# Loginator2368.net
KiCad netlist of a schematic drawn in EAGLE
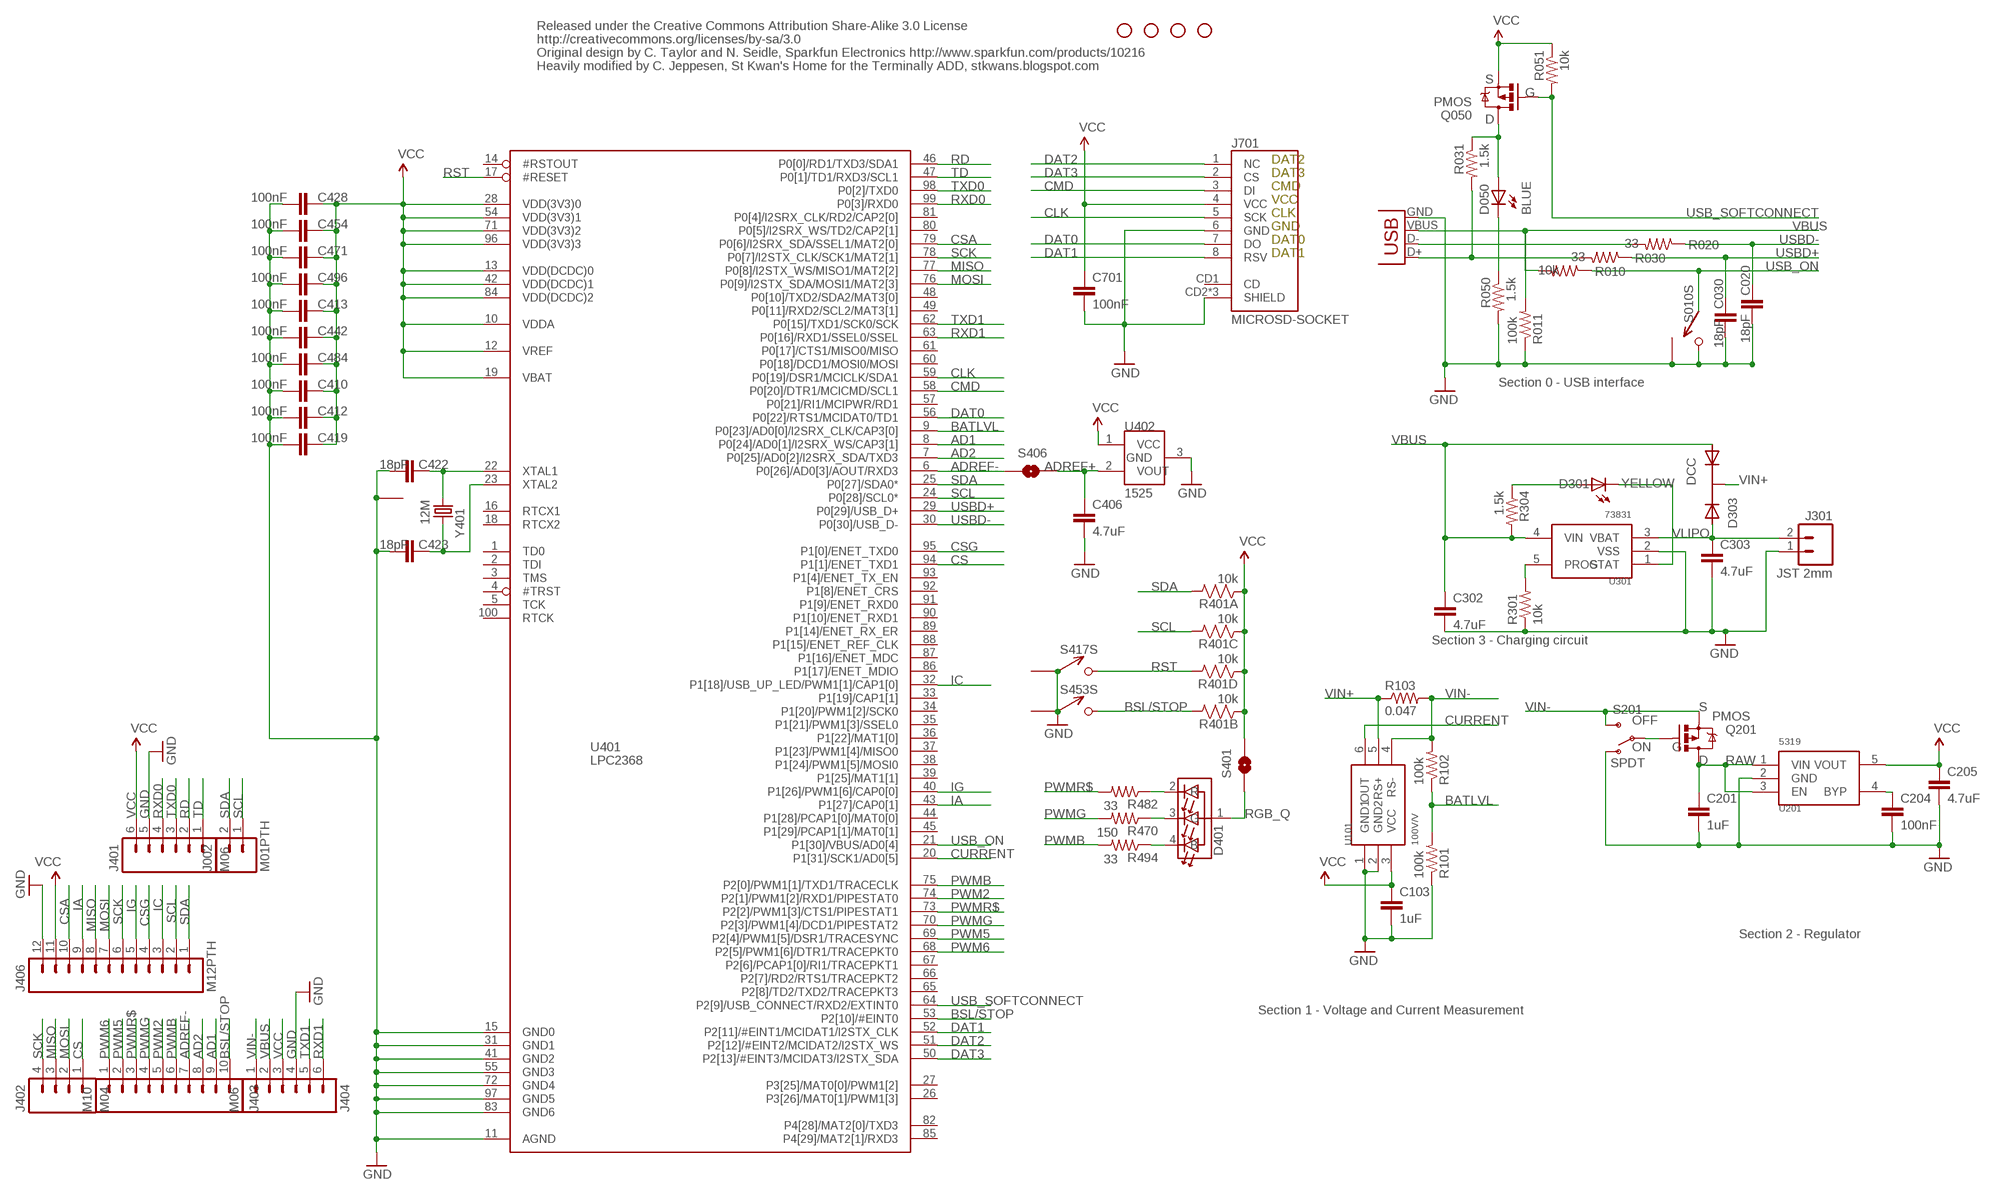
[diagram p0: schematic, sheet 1]

(export (version "E")
  (design (tool "Eeschema 10.0.6"))
  (components
    (comp (ref "C020")
      (value "18pF")
      (footprint "eagle-import:0402-CAP")
      (libsource (lib "eagle-import") (part "CAP0402-CAP"))
    )
    (comp (ref "C030")
      (value "18pF")
      (footprint "eagle-import:0402-CAP")
      (libsource (lib "eagle-import") (part "CAP0402-CAP"))
    )
    (comp (ref "C103")
      (value "1uF")
      (footprint "eagle-import:0402-CAP")
      (libsource (lib "eagle-import") (part "CAP0402-CAP"))
    )
    (comp (ref "C201")
      (value "1uF")
      (footprint "eagle-import:0402-CAP")
      (libsource (lib "eagle-import") (part "CAP0402-CAP"))
    )
    (comp (ref "C204")
      (value "100nF")
      (footprint "eagle-import:0402-CAP")
      (libsource (lib "eagle-import") (part "CAP0402-CAP"))
    )
    (comp (ref "C205")
      (value "4.7uF")
      (footprint "eagle-import:0402-CAP")
      (libsource (lib "eagle-import") (part "CAP0402-CAP"))
    )
    (comp (ref "C302")
      (value "4.7uF")
      (footprint "eagle-import:0402-CAP")
      (libsource (lib "eagle-import") (part "CAP0402-CAP"))
    )
    (comp (ref "C303")
      (value "4.7uF")
      (footprint "eagle-import:0402-CAP")
      (libsource (lib "eagle-import") (part "CAP0402-CAP"))
    )
    (comp (ref "C406")
      (value "4.7uF")
      (footprint "eagle-import:0402-CAP")
      (libsource (lib "eagle-import") (part "CAP0402-CAP"))
    )
    (comp (ref "C410")
      (value "100nF")
      (footprint "eagle-import:0402-CAP")
      (libsource (lib "eagle-import") (part "CAP0402-CAP"))
    )
    (comp (ref "C412")
      (value "100nF")
      (footprint "eagle-import:0402-CAP")
      (libsource (lib "eagle-import") (part "CAP0402-CAP"))
    )
    (comp (ref "C413")
      (value "100nF")
      (footprint "eagle-import:0402-CAP")
      (libsource (lib "eagle-import") (part "CAP0402-CAP"))
    )
    (comp (ref "C419")
      (value "100nF")
      (footprint "eagle-import:0402-CAP")
      (libsource (lib "eagle-import") (part "CAP0402-CAP"))
    )
    (comp (ref "C422")
      (value "18pF")
      (footprint "eagle-import:0402-CAP")
      (libsource (lib "eagle-import") (part "CAP0402-CAP"))
    )
    (comp (ref "C423")
      (value "18pF")
      (footprint "eagle-import:0402-CAP")
      (libsource (lib "eagle-import") (part "CAP0402-CAP"))
    )
    (comp (ref "C428")
      (value "100nF")
      (footprint "eagle-import:0402-CAP")
      (libsource (lib "eagle-import") (part "CAP0402-CAP"))
    )
    (comp (ref "C442")
      (value "100nF")
      (footprint "eagle-import:0402-CAP")
      (libsource (lib "eagle-import") (part "CAP0402-CAP"))
    )
    (comp (ref "C454")
      (value "100nF")
      (footprint "eagle-import:0402-CAP")
      (libsource (lib "eagle-import") (part "CAP0402-CAP"))
    )
    (comp (ref "C471")
      (value "100nF")
      (footprint "eagle-import:0402-CAP")
      (libsource (lib "eagle-import") (part "CAP0402-CAP"))
    )
    (comp (ref "C484")
      (value "100nF")
      (footprint "eagle-import:0402-CAP")
      (libsource (lib "eagle-import") (part "CAP0402-CAP"))
    )
    (comp (ref "C496")
      (value "100nF")
      (footprint "eagle-import:0402-CAP")
      (libsource (lib "eagle-import") (part "CAP0402-CAP"))
    )
    (comp (ref "C701")
      (value "100nF")
      (footprint "eagle-import:0402-CAP")
      (libsource (lib "eagle-import") (part "CAP0402-CAP"))
    )
    (comp (ref "D050")
      (value "BLUE")
      (footprint "eagle-import:LED-0603")
      (libsource (lib "eagle-import") (part "LED0603"))
    )
    (comp (ref "D301")
      (value "YELLOW")
      (footprint "eagle-import:LED-0603")
      (libsource (lib "eagle-import") (part "LED0603"))
    )
    (comp (ref "D303")
      (value "DCC")
      (footprint "eagle-import:SOT-23-3")
      (libsource (lib "eagle-import") (part "PMEG2005CT"))
    )
    (comp (ref "D401")
      (value "RGB")
      (footprint "eagle-import:HSMF-C118")
      (libsource (lib "eagle-import") (part "HSMF-C118"))
    )
    (comp (ref "J001")
      (value "USBSMD")
      (footprint "eagle-import:USB-MINIB")
      (libsource (lib "eagle-import") (part "USBSMD"))
    )
    (comp (ref "J002")
      (value "M01PTH")
      (footprint "eagle-import:1X02")
      (libsource (lib "eagle-import") (part "M02PTH"))
    )
    (comp (ref "J301")
      (value "JST 2mm")
      (footprint "eagle-import:JST-2-SMD")
      (libsource (lib "eagle-import") (part "M02-JST-2MM-SMT"))
    )
    (comp (ref "J401")
      (value "M06")
      (footprint "eagle-import:1X06")
      (libsource (lib "eagle-import") (part "M06SIP"))
    )
    (comp (ref "J402")
      (value "M04")
      (footprint "eagle-import:1X04")
      (libsource (lib "eagle-import") (part "M04PTH"))
    )
    (comp (ref "J403")
      (value "M10")
      (footprint "eagle-import:1X10")
      (libsource (lib "eagle-import") (part "M10{dblquote}"))
    )
    (comp (ref "J404")
      (value "M06")
      (footprint "eagle-import:1X06")
      (libsource (lib "eagle-import") (part "M06SIP"))
    )
    (comp (ref "J406")
      (value "M12PTH")
      (footprint "eagle-import:1X12")
      (libsource (lib "eagle-import") (part "M12PTH"))
    )
    (comp (ref "J701")
      (value "MICROSD-SOCKET")
      (footprint "eagle-import:MICROSD-SOCKET-PP")
      (libsource (lib "eagle-import") (part "MICROSD-SOCKET"))
    )
    (comp (ref "JP1")
      (value "STAND-OFF")
      (footprint "eagle-import:STAND-OFF")
      (libsource (lib "eagle-import") (part "STAND-OFF"))
    )
    (comp (ref "JP2")
      (value "STAND-OFF")
      (footprint "eagle-import:STAND-OFF")
      (libsource (lib "eagle-import") (part "STAND-OFF"))
    )
    (comp (ref "JP3")
      (value "STAND-OFF")
      (footprint "eagle-import:STAND-OFF")
      (libsource (lib "eagle-import") (part "STAND-OFF"))
    )
    (comp (ref "JP4")
      (value "STAND-OFF")
      (footprint "eagle-import:STAND-OFF")
      (libsource (lib "eagle-import") (part "STAND-OFF"))
    )
    (comp (ref "Q050")
      (value "PMOS")
      (footprint "eagle-import:SOT23-3")
      (libsource (lib "eagle-import") (part "MOSFET-PCHANNELSMD"))
    )
    (comp (ref "Q201")
      (value "PMOS")
      (footprint "eagle-import:SOT23-3")
      (libsource (lib "eagle-import") (part "MOSFET-PCHANNELSMD"))
    )
    (comp (ref "R010")
      (value "10k")
      (footprint "eagle-import:0402-RES")
      (libsource (lib "eagle-import") (part "RESISTOR0402-RES"))
    )
    (comp (ref "R011")
      (value "100k")
      (footprint "eagle-import:0402-RES")
      (libsource (lib "eagle-import") (part "RESISTOR0402-RES"))
    )
    (comp (ref "R020")
      (value "33")
      (footprint "eagle-import:0402-RES")
      (libsource (lib "eagle-import") (part "RESISTOR0402-RES"))
    )
    (comp (ref "R030")
      (value "33")
      (footprint "eagle-import:0402-RES")
      (libsource (lib "eagle-import") (part "RESISTOR0402-RES"))
    )
    (comp (ref "R031")
      (value "1.5k")
      (footprint "eagle-import:0402-RES")
      (libsource (lib "eagle-import") (part "RESISTOR0402-RES"))
    )
    (comp (ref "R050")
      (value "1.5k")
      (footprint "eagle-import:0402-RES")
      (libsource (lib "eagle-import") (part "RESISTOR0402-RES"))
    )
    (comp (ref "R051")
      (value "10k")
      (footprint "eagle-import:0402-RES")
      (libsource (lib "eagle-import") (part "RESISTOR0402-RES"))
    )
    (comp (ref "R101")
      (value "100k")
      (footprint "eagle-import:0402-RES")
      (libsource (lib "eagle-import") (part "RESISTOR0402-RES"))
    )
    (comp (ref "R102")
      (value "100k")
      (footprint "eagle-import:0402-RES")
      (libsource (lib "eagle-import") (part "RESISTOR0402-RES"))
    )
    (comp (ref "R103")
      (value "0.047")
      (footprint "eagle-import:0402-RES")
      (libsource (lib "eagle-import") (part "RESISTOR0402-RES"))
    )
    (comp (ref "R301")
      (value "10k")
      (footprint "eagle-import:0402-RES")
      (libsource (lib "eagle-import") (part "RESISTOR0402-RES"))
    )
    (comp (ref "R304")
      (value "1.5k")
      (footprint "eagle-import:0402-RES")
      (libsource (lib "eagle-import") (part "RESISTOR0402-RES"))
    )
    (comp (ref "R401")
      (value "10k")
      (footprint "eagle-import:CRA04")
      (fields (field (name "DIGIKEY") "CRA4S810KCT-ND"))
      (libsource (lib "eagle-import") (part "RP404"))
    )
    (comp (ref "R470")
      (value "150")
      (footprint "eagle-import:0402-RES")
      (libsource (lib "eagle-import") (part "RESISTOR0402-RES"))
    )
    (comp (ref "R482")
      (value "33")
      (footprint "eagle-import:0402-RES")
      (libsource (lib "eagle-import") (part "RESISTOR0402-RES"))
    )
    (comp (ref "R494")
      (value "33")
      (footprint "eagle-import:0402-RES")
      (libsource (lib "eagle-import") (part "RESISTOR0402-RES"))
    )
    (comp (ref "S010")
      (value "SPST")
      (footprint "eagle-import:B3U-1100P")
      (fields (field (name "DIGIKEY") "SW1021CT-ND"))
      (libsource (lib "eagle-import") (part "B3U-1100P"))
    )
    (comp (ref "S201")
      (value "SPDT")
      (footprint "eagle-import:AYZ0202")
      (libsource (lib "eagle-import") (part "SWITCH-SPSTSMD"))
    )
    (comp (ref "S401")
      (value "SOLDERJUMPERNO")
      (footprint "eagle-import:SJ_2S-NO")
      (libsource (lib "eagle-import") (part "SOLDERJUMPERNO"))
    )
    (comp (ref "S406")
      (value "SOLDERJUMPERNO")
      (footprint "eagle-import:SJ_2S-NO")
      (libsource (lib "eagle-import") (part "SOLDERJUMPERNO"))
    )
    (comp (ref "S417")
      (value "SPST")
      (footprint "eagle-import:B3U-1100P")
      (fields (field (name "DIGIKEY") "SW1021CT-ND"))
      (libsource (lib "eagle-import") (part "B3U-1100P"))
    )
    (comp (ref "S453")
      (value "SPST")
      (footprint "eagle-import:B3U-1100P")
      (fields (field (name "DIGIKEY") "SW1021CT-ND"))
      (libsource (lib "eagle-import") (part "B3U-1100P"))
    )
    (comp (ref "U101")
      (value "100V/V")
      (footprint "eagle-import:SOT-23-6")
      (libsource (lib "eagle-import") (part "MAX4173"))
    )
    (comp (ref "U201")
      (value "5319")
      (footprint "eagle-import:SOT-23-5")
      (libsource (lib "eagle-import") (part "MIC5319D5"))
    )
    (comp (ref "U301")
      (value "73831")
      (footprint "eagle-import:SOT-23-5")
      (libsource (lib "eagle-import") (part "MCP73831"))
    )
    (comp (ref "U401")
      (value "LPC2368")
      (footprint "eagle-import:LQFP100")
      (libsource (lib "eagle-import") (part "LPC2368"))
    )
    (comp (ref "U402")
      (value "1525")
      (footprint "eagle-import:SOT-23-3")
      (libsource (lib "eagle-import") (part "MCP1525"))
    )
    (comp (ref "Y401")
      (value "12M")
      (footprint "eagle-import:CRYSTAL_SMD")
      (fields (field (name "DIGIKEY") "887-1316-1-ND"))
      (libsource (lib "eagle-import") (part "TSX-3225"))
    )
  )
  (nets
    (net (code "1") (name "/AD1") (class "Default")
      (node (ref "J403") (pin "9") (pinfunction "9_9") (pintype "passive"))
      (node (ref "U401") (pin "8") (pinfunction "P0[24]/AD0[1]/I2SRX_WS/CAP3[1]_8") (pintype "bidirectional"))
    )
    (net (code "2") (name "/AD2") (class "Default")
      (node (ref "J403") (pin "8") (pinfunction "8_8") (pintype "passive"))
      (node (ref "U401") (pin "7") (pinfunction "P0[25]/AD0[2]/I2SRX_SDA/TXD3_7") (pintype "bidirectional"))
    )
    (net (code "3") (name "/ADREF+") (class "Default")
      (node (ref "C406") (pin "1") (pinfunction "1_1") (pintype "passive"))
      (node (ref "S406") (pin "1") (pinfunction "1_1") (pintype "passive"))
      (node (ref "U402") (pin "2") (pinfunction "VOUT_2") (pintype "bidirectional"))
    )
    (net (code "4") (name "/ADREF-") (class "Default")
      (node (ref "J403") (pin "7") (pinfunction "7_7") (pintype "passive"))
      (node (ref "S406") (pin "2") (pinfunction "2_2") (pintype "passive"))
      (node (ref "U401") (pin "6") (pinfunction "P0[26]/AD0[3]/AOUT/RXD3_6") (pintype "bidirectional"))
    )
    (net (code "5") (name "/BATLVL") (class "Default")
      (node (ref "R101") (pin "2") (pinfunction "2_2") (pintype "passive"))
      (node (ref "R102") (pin "1") (pinfunction "1_1") (pintype "passive"))
      (node (ref "U401") (pin "9") (pinfunction "P0[23]/AD0[0]/I2SRX_CLK/CAP3[0]_9") (pintype "bidirectional"))
    )
    (net (code "6") (name "/BSL{slash}STOP") (class "Default")
      (node (ref "J403") (pin "10") (pinfunction "10_10") (pintype "passive"))
      (node (ref "R401") (pin "7") (pinfunction "2_7") (pintype "passive"))
      (node (ref "S453") (pin "P$2") (pinfunction "2_P$2") (pintype "bidirectional"))
      (node (ref "U401") (pin "53") (pinfunction "P2[10]/#EINT0_53") (pintype "bidirectional"))
    )
    (net (code "7") (name "/CLK") (class "Default")
      (node (ref "J701") (pin "5") (pinfunction "SCK_5") (pintype "bidirectional"))
      (node (ref "U401") (pin "59") (pinfunction "P0[19]/DSR1/MCICLK/SDA1_59") (pintype "bidirectional"))
    )
    (net (code "8") (name "/CMD") (class "Default")
      (node (ref "J701") (pin "3") (pinfunction "DI_3") (pintype "bidirectional"))
      (node (ref "U401") (pin "58") (pinfunction "P0[20]/DTR1/MCICMD/SCL1_58") (pintype "bidirectional"))
    )
    (net (code "9") (name "/CS") (class "Default")
      (node (ref "J402") (pin "1") (pinfunction "1_1") (pintype "passive"))
      (node (ref "U401") (pin "94") (pinfunction "P1[1]/ENET_TXD1_94") (pintype "bidirectional"))
    )
    (net (code "10") (name "/CSA") (class "Default")
      (node (ref "J406") (pin "10") (pinfunction "10_10") (pintype "passive"))
      (node (ref "U401") (pin "79") (pinfunction "P0[6]/I2SRX_SDA/SSEL1/MAT2[0]_79") (pintype "bidirectional"))
    )
    (net (code "11") (name "/CSG") (class "Default")
      (node (ref "J406") (pin "4") (pinfunction "4_4") (pintype "passive"))
      (node (ref "U401") (pin "95") (pinfunction "P1[0]/ENET_TXD0_95") (pintype "bidirectional"))
    )
    (net (code "12") (name "/CURRENT") (class "Default")
      (node (ref "U101") (pin "6") (pinfunction "OUT_6") (pintype "bidirectional"))
      (node (ref "U401") (pin "20") (pinfunction "P1[31]/SCK1/AD0[5]_20") (pintype "bidirectional"))
    )
    (net (code "13") (name "/DAT0") (class "Default")
      (node (ref "J701") (pin "7") (pinfunction "DO_7") (pintype "bidirectional"))
      (node (ref "U401") (pin "56") (pinfunction "P0[22]/RTS1/MCIDAT0/TD1_56") (pintype "bidirectional"))
    )
    (net (code "14") (name "/DAT1") (class "Default")
      (node (ref "J701") (pin "8") (pinfunction "RSV_8") (pintype "bidirectional"))
      (node (ref "U401") (pin "52") (pinfunction "P2[11]/#EINT1/MCIDAT1/I2STX_CLK_52") (pintype "bidirectional"))
    )
    (net (code "15") (name "/DAT2") (class "Default")
      (node (ref "J701") (pin "1") (pinfunction "NC_1") (pintype "bidirectional"))
      (node (ref "U401") (pin "51") (pinfunction "P2[12]/#EINT2/MCIDAT2/I2STX_WS_51") (pintype "bidirectional"))
    )
    (net (code "16") (name "/DAT3") (class "Default")
      (node (ref "J701") (pin "2") (pinfunction "CS_2") (pintype "bidirectional"))
      (node (ref "U401") (pin "50") (pinfunction "P2[13]/#EINT3/MCIDAT3/I2STX_SDA_50") (pintype "bidirectional"))
    )
    (net (code "17") (name "/IA") (class "Default")
      (node (ref "J406") (pin "9") (pinfunction "9_9") (pintype "passive"))
      (node (ref "U401") (pin "43") (pinfunction "P1[27]/CAP0[1]_43") (pintype "bidirectional"))
    )
    (net (code "18") (name "/IC") (class "Default")
      (node (ref "J406") (pin "3") (pinfunction "3_3") (pintype "passive"))
      (node (ref "U401") (pin "32") (pinfunction "P1[18]/USB_UP_LED/PWM1[1]/CAP1[0]_32") (pintype "bidirectional"))
    )
    (net (code "19") (name "/IG") (class "Default")
      (node (ref "J406") (pin "5") (pinfunction "5_5") (pintype "passive"))
      (node (ref "U401") (pin "40") (pinfunction "P1[26]/PWM1[6]/CAP0[0]_40") (pintype "bidirectional"))
    )
    (net (code "20") (name "/MISO") (class "Default")
      (node (ref "J402") (pin "3") (pinfunction "3_3") (pintype "passive"))
      (node (ref "J406") (pin "8") (pinfunction "8_8") (pintype "passive"))
      (node (ref "U401") (pin "77") (pinfunction "P0[8]/I2STX_WS/MISO1/MAT2[2]_77") (pintype "bidirectional"))
    )
    (net (code "21") (name "/MOSI") (class "Default")
      (node (ref "J402") (pin "2") (pinfunction "2_2") (pintype "passive"))
      (node (ref "J406") (pin "7") (pinfunction "7_7") (pintype "passive"))
      (node (ref "U401") (pin "76") (pinfunction "P0[9]/I2STX_SDA/MOSI1/MAT2[3]_76") (pintype "bidirectional"))
    )
    (net (code "22") (name "/PWM2") (class "Default")
      (node (ref "J403") (pin "5") (pinfunction "5_5") (pintype "passive"))
      (node (ref "U401") (pin "74") (pinfunction "P2[1]/PWM1[2]/RXD1/PIPESTAT0_74") (pintype "bidirectional"))
    )
    (net (code "23") (name "/PWM5") (class "Default")
      (node (ref "J403") (pin "2") (pinfunction "2_2") (pintype "passive"))
      (node (ref "U401") (pin "69") (pinfunction "P2[4]/PWM1[5]/DSR1/TRACESYNC_69") (pintype "bidirectional"))
    )
    (net (code "24") (name "/PWM6") (class "Default")
      (node (ref "J403") (pin "1") (pinfunction "1_1") (pintype "passive"))
      (node (ref "U401") (pin "68") (pinfunction "P2[5]/PWM1[6]/DTR1/TRACEPKT0_68") (pintype "bidirectional"))
    )
    (net (code "25") (name "/PWMB") (class "Default")
      (node (ref "J403") (pin "6") (pinfunction "6_6") (pintype "passive"))
      (node (ref "R494") (pin "2") (pinfunction "2_2") (pintype "passive"))
      (node (ref "U401") (pin "75") (pinfunction "P2[0]/PWM1[1]/TXD1/TRACECLK_75") (pintype "bidirectional"))
    )
    (net (code "26") (name "/PWMG") (class "Default")
      (node (ref "J403") (pin "4") (pinfunction "4_4") (pintype "passive"))
      (node (ref "R470") (pin "2") (pinfunction "2_2") (pintype "passive"))
      (node (ref "U401") (pin "70") (pinfunction "P2[3]/PWM1[4]/DCD1/PIPESTAT2_70") (pintype "bidirectional"))
    )
    (net (code "27") (name "/PWMR$") (class "Default")
      (node (ref "J403") (pin "3") (pinfunction "3_3") (pintype "passive"))
      (node (ref "R482") (pin "2") (pinfunction "2_2") (pintype "passive"))
      (node (ref "U401") (pin "73") (pinfunction "P2[2]/PWM1[3]/CTS1/PIPESTAT1_73") (pintype "bidirectional"))
    )
    (net (code "28") (name "/RAW") (class "Default")
      (node (ref "C201") (pin "1") (pinfunction "1_1") (pintype "passive"))
      (node (ref "Q201") (pin "3") (pinfunction "D_3") (pintype "passive"))
      (node (ref "U201") (pin "1") (pinfunction "VIN_1") (pintype "bidirectional"))
      (node (ref "U201") (pin "3") (pinfunction "EN_3") (pintype "bidirectional"))
    )
    (net (code "29") (name "/RD") (class "Default")
      (node (ref "J401") (pin "2") (pinfunction "2_2") (pintype "passive"))
      (node (ref "U401") (pin "46") (pinfunction "P0[0]/RD1/TXD3/SDA1_46") (pintype "bidirectional"))
    )
    (net (code "30") (name "/RGB_Q") (class "Default")
      (node (ref "D401") (pin "1") (pinfunction "A_1") (pintype "passive"))
      (node (ref "S401") (pin "1") (pinfunction "1_1") (pintype "passive"))
    )
    (net (code "31") (name "/RST") (class "Default")
      (node (ref "R401") (pin "5") (pinfunction "2_5") (pintype "passive"))
      (node (ref "S417") (pin "P$2") (pinfunction "2_P$2") (pintype "bidirectional"))
      (node (ref "U401") (pin "17") (pinfunction "#RESET_17") (pintype "bidirectional"))
    )
    (net (code "32") (name "/RXD0") (class "Default")
      (node (ref "J401") (pin "4") (pinfunction "4_4") (pintype "passive"))
      (node (ref "U401") (pin "99") (pinfunction "P0[3]/RXD0_99") (pintype "bidirectional"))
    )
    (net (code "33") (name "/RXD1") (class "Default")
      (node (ref "J404") (pin "6") (pinfunction "6_6") (pintype "passive"))
      (node (ref "U401") (pin "63") (pinfunction "P0[16]/RXD1/SSEL0/SSEL_63") (pintype "bidirectional"))
    )
    (net (code "34") (name "/SCK") (class "Default")
      (node (ref "J402") (pin "4") (pinfunction "4_4") (pintype "passive"))
      (node (ref "J406") (pin "6") (pinfunction "6_6") (pintype "passive"))
      (node (ref "U401") (pin "78") (pinfunction "P0[7]/I2STX_CLK/SCK1/MAT2[1]_78") (pintype "bidirectional"))
    )
    (net (code "35") (name "/SCL") (class "Default")
      (node (ref "J002") (pin "1") (pinfunction "1_1") (pintype "passive"))
      (node (ref "J406") (pin "2") (pinfunction "2_2") (pintype "passive"))
      (node (ref "R401") (pin "6") (pinfunction "2_6") (pintype "passive"))
      (node (ref "U401") (pin "24") (pinfunction "P0[28]/SCL0*_24") (pintype "bidirectional"))
    )
    (net (code "36") (name "/SDA") (class "Default")
      (node (ref "J002") (pin "2") (pinfunction "2_2") (pintype "passive"))
      (node (ref "J406") (pin "1") (pinfunction "1_1") (pintype "passive"))
      (node (ref "R401") (pin "8") (pinfunction "2_8") (pintype "passive"))
      (node (ref "U401") (pin "25") (pinfunction "P0[27]/SDA0*_25") (pintype "bidirectional"))
    )
    (net (code "37") (name "/TD") (class "Default")
      (node (ref "J401") (pin "1") (pinfunction "1_1") (pintype "passive"))
      (node (ref "U401") (pin "47") (pinfunction "P0[1]/TD1/RXD3/SCL1_47") (pintype "bidirectional"))
    )
    (net (code "38") (name "/TXD0") (class "Default")
      (node (ref "J401") (pin "3") (pinfunction "3_3") (pintype "passive"))
      (node (ref "U401") (pin "98") (pinfunction "P0[2]/TXD0_98") (pintype "bidirectional"))
    )
    (net (code "39") (name "/TXD1") (class "Default")
      (node (ref "J404") (pin "5") (pinfunction "5_5") (pintype "passive"))
      (node (ref "U401") (pin "62") (pinfunction "P0[15]/TXD1/SCK0/SCK_62") (pintype "bidirectional"))
    )
    (net (code "40") (name "/USBD+") (class "Default")
      (node (ref "C030") (pin "1") (pinfunction "1_1") (pintype "passive"))
      (node (ref "R030") (pin "1") (pinfunction "1_1") (pintype "passive"))
      (node (ref "U401") (pin "29") (pinfunction "P0[29]/USB_D+_29") (pintype "bidirectional"))
    )
    (net (code "41") (name "/USBD-") (class "Default")
      (node (ref "C020") (pin "1") (pinfunction "1_1") (pintype "passive"))
      (node (ref "R020") (pin "1") (pinfunction "1_1") (pintype "passive"))
      (node (ref "U401") (pin "30") (pinfunction "P0[30]/USB_D-_30") (pintype "bidirectional"))
    )
    (net (code "42") (name "/USB_ON") (class "Default")
      (node (ref "R010") (pin "1") (pinfunction "1_1") (pintype "passive"))
      (node (ref "S010") (pin "P$1") (pinfunction "1_P$1") (pintype "bidirectional"))
      (node (ref "U401") (pin "21") (pinfunction "P1[30]/VBUS/AD0[4]_21") (pintype "bidirectional"))
    )
    (net (code "43") (name "/USB_SOFTCONNECT") (class "Default")
      (node (ref "Q050") (pin "1") (pinfunction "G_1") (pintype "passive"))
      (node (ref "R051") (pin "2") (pinfunction "2_2") (pintype "passive"))
      (node (ref "U401") (pin "64") (pinfunction "P2[9]/USB_CONNECT/RXD2/EXTINT0_64") (pintype "bidirectional"))
    )
    (net (code "44") (name "/VBUS") (class "Default")
      (node (ref "C302") (pin "1") (pinfunction "1_1") (pintype "passive"))
      (node (ref "D303") (pin "1") (pinfunction "A1_1") (pintype "passive"))
      (node (ref "J001") (pin "VBUS") (pinfunction "VBUS_VBUS") (pintype "bidirectional"))
      (node (ref "J404") (pin "2") (pinfunction "2_2") (pintype "passive"))
      (node (ref "R010") (pin "2") (pinfunction "2_2") (pintype "passive"))
      (node (ref "R011") (pin "2") (pinfunction "2_2") (pintype "passive"))
      (node (ref "R304") (pin "2") (pinfunction "2_2") (pintype "passive"))
      (node (ref "U301") (pin "4") (pinfunction "VIN_4") (pintype "bidirectional"))
    )
    (net (code "45") (name "/VIN+") (class "Default")
      (node (ref "D303") (pin "3") (pinfunction "K_3") (pintype "passive"))
      (node (ref "R103") (pin "1") (pinfunction "1_1") (pintype "passive"))
      (node (ref "U101") (pin "5") (pinfunction "RS+_5") (pintype "bidirectional"))
    )
    (net (code "46") (name "/VIN-") (class "Default")
      (node (ref "J404") (pin "1") (pinfunction "1_1") (pintype "passive"))
      (node (ref "Q201") (pin "2") (pinfunction "S_2") (pintype "passive"))
      (node (ref "R102") (pin "2") (pinfunction "2_2") (pintype "passive"))
      (node (ref "R103") (pin "2") (pinfunction "2_2") (pintype "passive"))
      (node (ref "S201") (pin "3") (pinfunction "S_3") (pintype "passive"))
      (node (ref "U101") (pin "4") (pinfunction "RS-_4") (pintype "bidirectional"))
    )
    (net (code "47") (name "/VLIPO") (class "Default")
      (node (ref "C303") (pin "1") (pinfunction "1_1") (pintype "passive"))
      (node (ref "D303") (pin "2") (pinfunction "A2_2") (pintype "passive"))
      (node (ref "J301") (pin "2") (pinfunction "2_2") (pintype "passive"))
      (node (ref "U301") (pin "3") (pinfunction "VBAT_3") (pintype "bidirectional"))
    )
    (net (code "48") (name "GND") (class "Default")
      (node (ref "C020") (pin "2") (pinfunction "2_2") (pintype "passive"))
      (node (ref "C030") (pin "2") (pinfunction "2_2") (pintype "passive"))
      (node (ref "C103") (pin "2") (pinfunction "2_2") (pintype "passive"))
      (node (ref "C201") (pin "2") (pinfunction "2_2") (pintype "passive"))
      (node (ref "C204") (pin "2") (pinfunction "2_2") (pintype "passive"))
      (node (ref "C205") (pin "2") (pinfunction "2_2") (pintype "passive"))
      (node (ref "C302") (pin "2") (pinfunction "2_2") (pintype "passive"))
      (node (ref "C303") (pin "2") (pinfunction "2_2") (pintype "passive"))
      (node (ref "C406") (pin "2") (pinfunction "2_2") (pintype "passive"))
      (node (ref "C410") (pin "2") (pinfunction "2_2") (pintype "passive"))
      (node (ref "C412") (pin "2") (pinfunction "2_2") (pintype "passive"))
      (node (ref "C413") (pin "2") (pinfunction "2_2") (pintype "passive"))
      (node (ref "C419") (pin "2") (pinfunction "2_2") (pintype "passive"))
      (node (ref "C422") (pin "1") (pinfunction "1_1") (pintype "passive"))
      (node (ref "C423") (pin "1") (pinfunction "1_1") (pintype "passive"))
      (node (ref "C428") (pin "2") (pinfunction "2_2") (pintype "passive"))
      (node (ref "C442") (pin "2") (pinfunction "2_2") (pintype "passive"))
      (node (ref "C454") (pin "2") (pinfunction "2_2") (pintype "passive"))
      (node (ref "C471") (pin "2") (pinfunction "2_2") (pintype "passive"))
      (node (ref "C484") (pin "2") (pinfunction "2_2") (pintype "passive"))
      (node (ref "C496") (pin "2") (pinfunction "2_2") (pintype "passive"))
      (node (ref "C701") (pin "2") (pinfunction "2_2") (pintype "passive"))
      (node (ref "J001") (pin "GND") (pinfunction "GND_GND") (pintype "bidirectional"))
      (node (ref "J301") (pin "1") (pinfunction "1_1") (pintype "passive"))
      (node (ref "J401") (pin "5") (pinfunction "5_5") (pintype "passive"))
      (node (ref "J404") (pin "4") (pinfunction "4_4") (pintype "passive"))
      (node (ref "J406") (pin "12") (pinfunction "12_12") (pintype "passive"))
      (node (ref "J701") (pin "6") (pinfunction "GND_6") (pintype "bidirectional"))
      (node (ref "J701") (pin "CD2") (pinfunction "SHIELD_CD2") (pintype "bidirectional"))
      (node (ref "J701") (pin "GND1") (pinfunction "SHIELD_GND1") (pintype "bidirectional"))
      (node (ref "J701") (pin "GND3") (pinfunction "SHIELD_GND3") (pintype "bidirectional"))
      (node (ref "R011") (pin "1") (pinfunction "1_1") (pintype "passive"))
      (node (ref "R050") (pin "2") (pinfunction "2_2") (pintype "passive"))
      (node (ref "R101") (pin "1") (pinfunction "1_1") (pintype "passive"))
      (node (ref "R301") (pin "1") (pinfunction "1_1") (pintype "passive"))
      (node (ref "S010") (pin "P$2") (pinfunction "2_P$2") (pintype "bidirectional"))
      (node (ref "S010") (pin "P$3") (pinfunction "1_P$3") (pintype "bidirectional"))
      (node (ref "S201") (pin "1") (pinfunction "O_1") (pintype "passive"))
      (node (ref "S417") (pin "P$1") (pinfunction "1_P$1") (pintype "bidirectional"))
      (node (ref "S417") (pin "P$3") (pinfunction "1_P$3") (pintype "bidirectional"))
      (node (ref "S453") (pin "P$1") (pinfunction "1_P$1") (pintype "bidirectional"))
      (node (ref "S453") (pin "P$3") (pinfunction "1_P$3") (pintype "bidirectional"))
      (node (ref "U101") (pin "1") (pinfunction "GND1_1") (pintype "bidirectional"))
      (node (ref "U101") (pin "2") (pinfunction "GND2_2") (pintype "bidirectional"))
      (node (ref "U201") (pin "2") (pinfunction "GND_2") (pintype "bidirectional"))
      (node (ref "U301") (pin "2") (pinfunction "VSS_2") (pintype "bidirectional"))
      (node (ref "U401") (pin "11") (pinfunction "AGND_11") (pintype "bidirectional"))
      (node (ref "U401") (pin "15") (pinfunction "GND0_15") (pintype "bidirectional"))
      (node (ref "U401") (pin "31") (pinfunction "GND1_31") (pintype "bidirectional"))
      (node (ref "U401") (pin "41") (pinfunction "GND2_41") (pintype "bidirectional"))
      (node (ref "U401") (pin "55") (pinfunction "GND3_55") (pintype "bidirectional"))
      (node (ref "U401") (pin "72") (pinfunction "GND4_72") (pintype "bidirectional"))
      (node (ref "U401") (pin "83") (pinfunction "GND6_83") (pintype "bidirectional"))
      (node (ref "U401") (pin "97") (pinfunction "GND5_97") (pintype "bidirectional"))
      (node (ref "U402") (pin "3") (pinfunction "GND_3") (pintype "bidirectional"))
      (node (ref "Y401") (pin "2") (pinfunction "1_2") (pintype "bidirectional"))
      (node (ref "Y401") (pin "4") (pinfunction "1_4") (pintype "bidirectional"))
    )
    (net (code "49") (name "Net-(D050-PadC)") (class "Default")
      (node (ref "D050") (pin "C") (pinfunction "C_C") (pintype "passive"))
      (node (ref "R050") (pin "1") (pinfunction "1_1") (pintype "passive"))
    )
    (net (code "50") (name "Net-(D301-PadA)") (class "Default")
      (node (ref "D301") (pin "A") (pinfunction "A_A") (pintype "passive"))
      (node (ref "R304") (pin "1") (pinfunction "1_1") (pintype "passive"))
    )
    (net (code "51") (name "Net-(D401-B)") (class "Default")
      (node (ref "D401") (pin "4") (pinfunction "B_4") (pintype "passive"))
      (node (ref "R494") (pin "1") (pinfunction "1_1") (pintype "passive"))
    )
    (net (code "52") (name "Net-(D401-G)") (class "Default")
      (node (ref "D401") (pin "3") (pinfunction "G_3") (pintype "passive"))
      (node (ref "R470") (pin "1") (pinfunction "1_1") (pintype "passive"))
    )
    (net (code "53") (name "Net-(D401-R)") (class "Default")
      (node (ref "D401") (pin "2") (pinfunction "R_2") (pintype "passive"))
      (node (ref "R482") (pin "1") (pinfunction "1_1") (pintype "passive"))
    )
    (net (code "54") (name "Net-(J001-PadD+)") (class "Default")
      (node (ref "J001") (pin "D+") (pinfunction "D+_D+") (pintype "bidirectional"))
      (node (ref "R030") (pin "2") (pinfunction "2_2") (pintype "passive"))
      (node (ref "R031") (pin "2") (pinfunction "2_2") (pintype "passive"))
    )
    (net (code "55") (name "Net-(J001-PadD-)") (class "Default")
      (node (ref "J001") (pin "D-") (pinfunction "D-_D-") (pintype "bidirectional"))
      (node (ref "R020") (pin "2") (pinfunction "2_2") (pintype "passive"))
    )
    (net (code "56") (name "Net-(Q050-D)") (class "Default")
      (node (ref "D050") (pin "A") (pinfunction "A_A") (pintype "passive"))
      (node (ref "Q050") (pin "3") (pinfunction "D_3") (pintype "passive"))
      (node (ref "R031") (pin "1") (pinfunction "1_1") (pintype "passive"))
    )
    (net (code "57") (name "Net-(Q201-G)") (class "Default")
      (node (ref "Q201") (pin "1") (pinfunction "G_1") (pintype "passive"))
      (node (ref "S201") (pin "2") (pinfunction "P_2") (pintype "passive"))
    )
    (net (code "58") (name "Net-(U201-BYP)") (class "Default")
      (node (ref "C204") (pin "1") (pinfunction "1_1") (pintype "passive"))
      (node (ref "U201") (pin "4") (pinfunction "BYP_4") (pintype "bidirectional"))
    )
    (net (code "59") (name "Net-(U301-PROG)") (class "Default")
      (node (ref "R301") (pin "2") (pinfunction "2_2") (pintype "passive"))
      (node (ref "U301") (pin "5") (pinfunction "PROG_5") (pintype "bidirectional"))
    )
    (net (code "60") (name "Net-(U301-STAT)") (class "Default")
      (node (ref "D301") (pin "C") (pinfunction "C_C") (pintype "passive"))
      (node (ref "U301") (pin "1") (pinfunction "STAT_1") (pintype "bidirectional"))
    )
    (net (code "61") (name "Net-(U401-XTAL1)") (class "Default")
      (node (ref "C422") (pin "2") (pinfunction "2_2") (pintype "passive"))
      (node (ref "U401") (pin "22") (pinfunction "XTAL1_22") (pintype "bidirectional"))
      (node (ref "Y401") (pin "3") (pinfunction "2_3") (pintype "passive"))
    )
    (net (code "62") (name "Net-(U401-XTAL2)") (class "Default")
      (node (ref "C423") (pin "2") (pinfunction "2_2") (pintype "passive"))
      (node (ref "U401") (pin "23") (pinfunction "XTAL2_23") (pintype "bidirectional"))
      (node (ref "Y401") (pin "1") (pinfunction "1_1") (pintype "passive"))
    )
    (net (code "63") (name "VCC") (class "Default")
      (node (ref "C103") (pin "1") (pinfunction "1_1") (pintype "passive"))
      (node (ref "C205") (pin "1") (pinfunction "1_1") (pintype "passive"))
      (node (ref "C410") (pin "1") (pinfunction "1_1") (pintype "passive"))
      (node (ref "C412") (pin "1") (pinfunction "1_1") (pintype "passive"))
      (node (ref "C413") (pin "1") (pinfunction "1_1") (pintype "passive"))
      (node (ref "C419") (pin "1") (pinfunction "1_1") (pintype "passive"))
      (node (ref "C428") (pin "1") (pinfunction "1_1") (pintype "passive"))
      (node (ref "C442") (pin "1") (pinfunction "1_1") (pintype "passive"))
      (node (ref "C454") (pin "1") (pinfunction "1_1") (pintype "passive"))
      (node (ref "C471") (pin "1") (pinfunction "1_1") (pintype "passive"))
      (node (ref "C484") (pin "1") (pinfunction "1_1") (pintype "passive"))
      (node (ref "C496") (pin "1") (pinfunction "1_1") (pintype "passive"))
      (node (ref "C701") (pin "1") (pinfunction "1_1") (pintype "passive"))
      (node (ref "J401") (pin "6") (pinfunction "6_6") (pintype "passive"))
      (node (ref "J404") (pin "3") (pinfunction "3_3") (pintype "passive"))
      (node (ref "J406") (pin "11") (pinfunction "11_11") (pintype "passive"))
      (node (ref "J701") (pin "4") (pinfunction "VCC_4") (pintype "bidirectional"))
      (node (ref "Q050") (pin "2") (pinfunction "S_2") (pintype "passive"))
      (node (ref "R051") (pin "1") (pinfunction "1_1") (pintype "passive"))
      (node (ref "R401") (pin "1") (pinfunction "1_1") (pintype "passive"))
      (node (ref "R401") (pin "2") (pinfunction "1_2") (pintype "passive"))
      (node (ref "R401") (pin "3") (pinfunction "1_3") (pintype "passive"))
      (node (ref "R401") (pin "4") (pinfunction "1_4") (pintype "passive"))
      (node (ref "S401") (pin "2") (pinfunction "2_2") (pintype "passive"))
      (node (ref "U101") (pin "3") (pinfunction "VCC_3") (pintype "bidirectional"))
      (node (ref "U201") (pin "5") (pinfunction "VOUT_5") (pintype "bidirectional"))
      (node (ref "U401") (pin "10") (pinfunction "VDDA_10") (pintype "bidirectional"))
      (node (ref "U401") (pin "12") (pinfunction "VREF_12") (pintype "bidirectional"))
      (node (ref "U401") (pin "13") (pinfunction "VDD(DCDC)0_13") (pintype "bidirectional"))
      (node (ref "U401") (pin "19") (pinfunction "VBAT_19") (pintype "bidirectional"))
      (node (ref "U401") (pin "28") (pinfunction "VDD(3V3)0_28") (pintype "bidirectional"))
      (node (ref "U401") (pin "42") (pinfunction "VDD(DCDC)1_42") (pintype "bidirectional"))
      (node (ref "U401") (pin "54") (pinfunction "VDD(3V3)1_54") (pintype "bidirectional"))
      (node (ref "U401") (pin "71") (pinfunction "VDD(3V3)2_71") (pintype "bidirectional"))
      (node (ref "U401") (pin "84") (pinfunction "VDD(DCDC)2_84") (pintype "bidirectional"))
      (node (ref "U401") (pin "96") (pinfunction "VDD(3V3)3_96") (pintype "bidirectional"))
      (node (ref "U402") (pin "1") (pinfunction "VCC_1") (pintype "bidirectional"))
    )
    (net (code "64") (name "unconnected-(J701-CD-PadCD1)") (class "Default")
      (node (ref "J701") (pin "CD1") (pinfunction "CD_CD1") (pintype "bidirectional"))
    )
    (net (code "65") (name "unconnected-(U401-#RSTOUT-Pad14)") (class "Default")
      (node (ref "U401") (pin "14") (pinfunction "#RSTOUT_14") (pintype "bidirectional"))
    )
    (net (code "66") (name "unconnected-(U401-#TRST-Pad4)") (class "Default")
      (node (ref "U401") (pin "4") (pinfunction "#TRST_4") (pintype "bidirectional"))
    )
    (net (code "67") (name "unconnected-(U401-P0[4]{slash}I2SRX_CLK{slash}RD2{slash}CAP2[0]-Pad81)") (class "Default")
      (node (ref "U401") (pin "81") (pinfunction "P0[4]/I2SRX_CLK/RD2/CAP2[0]_81") (pintype "bidirectional"))
    )
    (net (code "68") (name "unconnected-(U401-P0[5]{slash}I2SRX_WS{slash}TD2{slash}CAP2[1]-Pad80)") (class "Default")
      (node (ref "U401") (pin "80") (pinfunction "P0[5]/I2SRX_WS/TD2/CAP2[1]_80") (pintype "bidirectional"))
    )
    (net (code "69") (name "unconnected-(U401-P0[10]{slash}TXD2{slash}SDA2{slash}MAT3[0]-Pad48)") (class "Default")
      (node (ref "U401") (pin "48") (pinfunction "P0[10]/TXD2/SDA2/MAT3[0]_48") (pintype "bidirectional"))
    )
    (net (code "70") (name "unconnected-(U401-P0[11]{slash}RXD2{slash}SCL2{slash}MAT3[1]-Pad49)") (class "Default")
      (node (ref "U401") (pin "49") (pinfunction "P0[11]/RXD2/SCL2/MAT3[1]_49") (pintype "bidirectional"))
    )
    (net (code "71") (name "unconnected-(U401-P0[17]{slash}CTS1{slash}MISO0{slash}MISO-Pad61)") (class "Default")
      (node (ref "U401") (pin "61") (pinfunction "P0[17]/CTS1/MISO0/MISO_61") (pintype "bidirectional"))
    )
    (net (code "72") (name "unconnected-(U401-P0[18]{slash}DCD1{slash}MOSI0{slash}MOSI-Pad60)") (class "Default")
      (node (ref "U401") (pin "60") (pinfunction "P0[18]/DCD1/MOSI0/MOSI_60") (pintype "bidirectional"))
    )
    (net (code "73") (name "unconnected-(U401-P0[21]{slash}RI1{slash}MCIPWR{slash}RD1-Pad57)") (class "Default")
      (node (ref "U401") (pin "57") (pinfunction "P0[21]/RI1/MCIPWR/RD1_57") (pintype "bidirectional"))
    )
    (net (code "74") (name "unconnected-(U401-P1[4]{slash}ENET_TX_EN-Pad93)") (class "Default")
      (node (ref "U401") (pin "93") (pinfunction "P1[4]/ENET_TX_EN_93") (pintype "bidirectional"))
    )
    (net (code "75") (name "unconnected-(U401-P1[8]{slash}ENET_CRS-Pad92)") (class "Default")
      (node (ref "U401") (pin "92") (pinfunction "P1[8]/ENET_CRS_92") (pintype "bidirectional"))
    )
    (net (code "76") (name "unconnected-(U401-P1[9]{slash}ENET_RXD0-Pad91)") (class "Default")
      (node (ref "U401") (pin "91") (pinfunction "P1[9]/ENET_RXD0_91") (pintype "bidirectional"))
    )
    (net (code "77") (name "unconnected-(U401-P1[10]{slash}ENET_RXD1-Pad90)") (class "Default")
      (node (ref "U401") (pin "90") (pinfunction "P1[10]/ENET_RXD1_90") (pintype "bidirectional"))
    )
    (net (code "78") (name "unconnected-(U401-P1[14]{slash}ENET_RX_ER-Pad89)") (class "Default")
      (node (ref "U401") (pin "89") (pinfunction "P1[14]/ENET_RX_ER_89") (pintype "bidirectional"))
    )
    (net (code "79") (name "unconnected-(U401-P1[15]{slash}ENET_REF_CLK-Pad88)") (class "Default")
      (node (ref "U401") (pin "88") (pinfunction "P1[15]/ENET_REF_CLK_88") (pintype "bidirectional"))
    )
    (net (code "80") (name "unconnected-(U401-P1[16]{slash}ENET_MDC-Pad87)") (class "Default")
      (node (ref "U401") (pin "87") (pinfunction "P1[16]/ENET_MDC_87") (pintype "bidirectional"))
    )
    (net (code "81") (name "unconnected-(U401-P1[17]{slash}ENET_MDIO-Pad86)") (class "Default")
      (node (ref "U401") (pin "86") (pinfunction "P1[17]/ENET_MDIO_86") (pintype "bidirectional"))
    )
    (net (code "82") (name "unconnected-(U401-P1[19]{slash}CAP1[1]-Pad33)") (class "Default")
      (node (ref "U401") (pin "33") (pinfunction "P1[19]/CAP1[1]_33") (pintype "bidirectional"))
    )
    (net (code "83") (name "unconnected-(U401-P1[20]{slash}PWM1[2]{slash}SCK0-Pad34)") (class "Default")
      (node (ref "U401") (pin "34") (pinfunction "P1[20]/PWM1[2]/SCK0_34") (pintype "bidirectional"))
    )
    (net (code "84") (name "unconnected-(U401-P1[21]{slash}PWM1[3]{slash}SSEL0-Pad35)") (class "Default")
      (node (ref "U401") (pin "35") (pinfunction "P1[21]/PWM1[3]/SSEL0_35") (pintype "bidirectional"))
    )
    (net (code "85") (name "unconnected-(U401-P1[22]{slash}MAT1[0]-Pad36)") (class "Default")
      (node (ref "U401") (pin "36") (pinfunction "P1[22]/MAT1[0]_36") (pintype "bidirectional"))
    )
    (net (code "86") (name "unconnected-(U401-P1[23]{slash}PWM1[4]{slash}MISO0-Pad37)") (class "Default")
      (node (ref "U401") (pin "37") (pinfunction "P1[23]/PWM1[4]/MISO0_37") (pintype "bidirectional"))
    )
    (net (code "87") (name "unconnected-(U401-P1[24]{slash}PWM1[5]{slash}MOSI0-Pad38)") (class "Default")
      (node (ref "U401") (pin "38") (pinfunction "P1[24]/PWM1[5]/MOSI0_38") (pintype "bidirectional"))
    )
    (net (code "88") (name "unconnected-(U401-P1[25]{slash}MAT1[1]-Pad39)") (class "Default")
      (node (ref "U401") (pin "39") (pinfunction "P1[25]/MAT1[1]_39") (pintype "bidirectional"))
    )
    (net (code "89") (name "unconnected-(U401-P1[28]{slash}PCAP1[0]{slash}MAT0[0]-Pad44)") (class "Default")
      (node (ref "U401") (pin "44") (pinfunction "P1[28]/PCAP1[0]/MAT0[0]_44") (pintype "bidirectional"))
    )
    (net (code "90") (name "unconnected-(U401-P1[29]{slash}PCAP1[1]{slash}MAT0[1]-Pad45)") (class "Default")
      (node (ref "U401") (pin "45") (pinfunction "P1[29]/PCAP1[1]/MAT0[1]_45") (pintype "bidirectional"))
    )
    (net (code "91") (name "unconnected-(U401-P2[6]{slash}PCAP1[0]{slash}RI1{slash}TRACEPKT1-Pad67)") (class "Default")
      (node (ref "U401") (pin "67") (pinfunction "P2[6]/PCAP1[0]/RI1/TRACEPKT1_67") (pintype "bidirectional"))
    )
    (net (code "92") (name "unconnected-(U401-P2[7]{slash}RD2{slash}RTS1{slash}TRACEPKT2-Pad66)") (class "Default")
      (node (ref "U401") (pin "66") (pinfunction "P2[7]/RD2/RTS1/TRACEPKT2_66") (pintype "bidirectional"))
    )
    (net (code "93") (name "unconnected-(U401-P2[8]{slash}TD2{slash}TXD2{slash}TRACEPKT3-Pad65)") (class "Default")
      (node (ref "U401") (pin "65") (pinfunction "P2[8]/TD2/TXD2/TRACEPKT3_65") (pintype "bidirectional"))
    )
    (net (code "94") (name "unconnected-(U401-P3[25]{slash}MAT0[0]{slash}PWM1[2]-Pad27)") (class "Default")
      (node (ref "U401") (pin "27") (pinfunction "P3[25]/MAT0[0]/PWM1[2]_27") (pintype "bidirectional"))
    )
    (net (code "95") (name "unconnected-(U401-P3[26]{slash}MAT0[1]{slash}PWM1[3]-Pad26)") (class "Default")
      (node (ref "U401") (pin "26") (pinfunction "P3[26]/MAT0[1]/PWM1[3]_26") (pintype "bidirectional"))
    )
    (net (code "96") (name "unconnected-(U401-P4[28]{slash}MAT2[0]{slash}TXD3-Pad82)") (class "Default")
      (node (ref "U401") (pin "82") (pinfunction "P4[28]/MAT2[0]/TXD3_82") (pintype "bidirectional"))
    )
    (net (code "97") (name "unconnected-(U401-P4[29]{slash}MAT2[1]{slash}RXD3-Pad85)") (class "Default")
      (node (ref "U401") (pin "85") (pinfunction "P4[29]/MAT2[1]/RXD3_85") (pintype "bidirectional"))
    )
    (net (code "98") (name "unconnected-(U401-RTCK-Pad100)") (class "Default")
      (node (ref "U401") (pin "100") (pinfunction "RTCK_100") (pintype "bidirectional"))
    )
    (net (code "99") (name "unconnected-(U401-RTCX1-Pad16)") (class "Default")
      (node (ref "U401") (pin "16") (pinfunction "RTCX1_16") (pintype "bidirectional"))
    )
    (net (code "100") (name "unconnected-(U401-RTCX2-Pad18)") (class "Default")
      (node (ref "U401") (pin "18") (pinfunction "RTCX2_18") (pintype "bidirectional"))
    )
    (net (code "101") (name "unconnected-(U401-TCK-Pad5)") (class "Default")
      (node (ref "U401") (pin "5") (pinfunction "TCK_5") (pintype "bidirectional"))
    )
    (net (code "102") (name "unconnected-(U401-TD0-Pad1)") (class "Default")
      (node (ref "U401") (pin "1") (pinfunction "TD0_1") (pintype "bidirectional"))
    )
    (net (code "103") (name "unconnected-(U401-TDI-Pad2)") (class "Default")
      (node (ref "U401") (pin "2") (pinfunction "TDI_2") (pintype "bidirectional"))
    )
    (net (code "104") (name "unconnected-(U401-TMS-Pad3)") (class "Default")
      (node (ref "U401") (pin "3") (pinfunction "TMS_3") (pintype "bidirectional"))
    )
  )
)
